# pcb-name-card.net
KiCad netlist of a schematic drawn in EAGLE
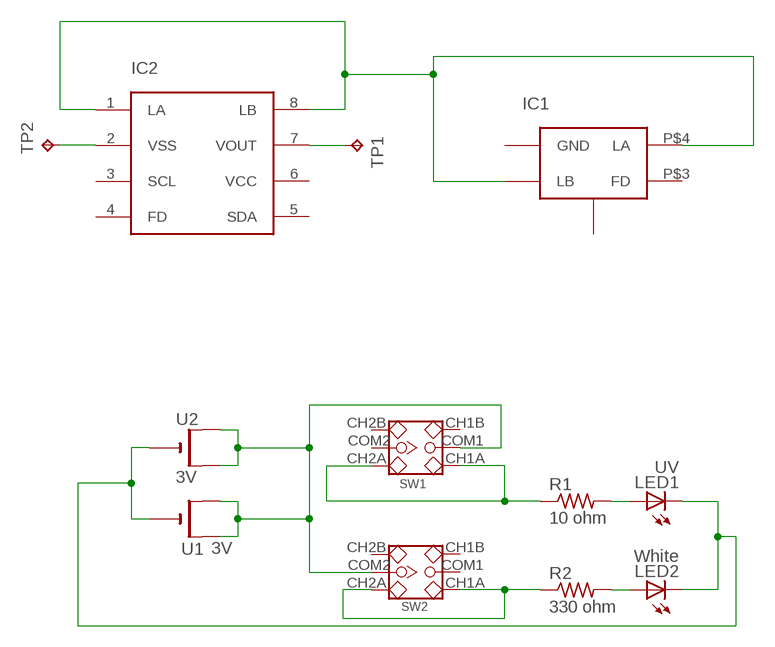
[diagram p0: schematic, sheet 1]

(export (version "E")
  (design (tool "Eeschema 10.0.6"))
  (components
    (comp (ref "IC1")
      (value "NTAG21XFDRC-FIT")
      (footprint "eagle-import:HXSON4-SMALL")
      (libsource (lib "eagle-import") (part "NTAG21XFDRC-FIT"))
    )
    (comp (ref "IC2")
      (value "NT3H1X01W0FTT")
      (footprint "eagle-import:TSSOP-8")
      (libsource (lib "eagle-import") (part "NT3H1X01W0FTT"))
    )
    (comp (ref "LED1")
      (value "UV")
      (footprint "eagle-import:PLCC2")
      (libsource (lib "eagle-import") (part "_T679-?-1D2E2LY"))
    )
    (comp (ref "LED2")
      (value "White")
      (footprint "eagle-import:PLCC2")
      (libsource (lib "eagle-import") (part "_T679-?-1D2E2LY"))
    )
    (comp (ref "R1")
      (value "10 ohm")
      (footprint "eagle-import:R2010")
      (libsource (lib "eagle-import") (part "R-US_R2010"))
    )
    (comp (ref "R2")
      (value "330 ohm")
      (footprint "eagle-import:R2010")
      (libsource (lib "eagle-import") (part "R-US_R2010"))
    )
    (comp (ref "SW1")
      (value "SMD-TOGGLE-SWITCH-2CH(2X3P-7X3.5MM)")
      (footprint "eagle-import:SW6-2.54-SMD-7.0X3.5X1.5MM")
      (fields (field (name "MPN") "MS-22C01"))
      (libsource (lib "eagle-import") (part "SMD-TOGGLE-SWITCH-2CH(2X3P-7X3.5MM)"))
    )
    (comp (ref "SW2")
      (value "SMD-TOGGLE-SWITCH-2CH(2X3P-7X3.5MM)")
      (footprint "eagle-import:SW6-2.54-SMD-7.0X3.5X1.5MM")
      (fields (field (name "MPN") "MS-22C01"))
      (libsource (lib "eagle-import") (part "SMD-TOGGLE-SWITCH-2CH(2X3P-7X3.5MM)"))
    )
    (comp (ref "TP1")
      (value "VOUT")
      (footprint "eagle-import:B2,54")
      (libsource (lib "eagle-import") (part "TPB2,54"))
    )
    (comp (ref "TP2")
      (value "GND")
      (footprint "eagle-import:B2,54")
      (libsource (lib "eagle-import") (part "TPB2,54"))
    )
    (comp (ref "U1")
      (value "3V")
      (footprint "eagle-import:CR2032-SMD")
      (libsource (lib "eagle-import") (part "CR2032SMT"))
    )
    (comp (ref "U2")
      (value "3V")
      (footprint "eagle-import:CR2032-SMD")
      (libsource (lib "eagle-import") (part "CR2032SMT"))
    )
  )
  (nets
    (net (code "1") (name "Net-(IC1-LA)") (class "Default")
      (node (ref "IC1") (pin "P$2") (pinfunction "LB_P$2") (pintype "bidirectional"))
      (node (ref "IC1") (pin "P$4") (pinfunction "LA_P$4") (pintype "bidirectional"))
      (node (ref "IC2") (pin "1") (pinfunction "LA_1") (pintype "bidirectional"))
      (node (ref "IC2") (pin "8") (pinfunction "LB_8") (pintype "bidirectional"))
    )
    (net (code "2") (name "Net-(IC2-VOUT)") (class "Default")
      (node (ref "IC2") (pin "7") (pinfunction "VOUT_7") (pintype "bidirectional"))
      (node (ref "TP1") (pin "TP") (pinfunction "TP_TP") (pintype "input"))
    )
    (net (code "3") (name "Net-(IC2-VSS)") (class "Default")
      (node (ref "IC2") (pin "2") (pinfunction "VSS_2") (pintype "bidirectional"))
      (node (ref "TP2") (pin "TP") (pinfunction "TP_TP") (pintype "input"))
    )
    (net (code "4") (name "Net-(LED1-PadA)") (class "Default")
      (node (ref "LED1") (pin "A") (pinfunction "A_A") (pintype "passive"))
      (node (ref "R1") (pin "2") (pinfunction "2_2") (pintype "passive"))
    )
    (net (code "5") (name "Net-(LED1-PadC)") (class "Default")
      (node (ref "LED1") (pin "C") (pinfunction "C_C") (pintype "passive"))
      (node (ref "LED2") (pin "C") (pinfunction "C_C") (pintype "passive"))
      (node (ref "U1") (pin "-") (pinfunction "-_-") (pintype "passive"))
      (node (ref "U2") (pin "-") (pinfunction "-_-") (pintype "passive"))
    )
    (net (code "6") (name "Net-(LED2-PadA)") (class "Default")
      (node (ref "LED2") (pin "A") (pinfunction "A_A") (pintype "passive"))
      (node (ref "R2") (pin "2") (pinfunction "2_2") (pintype "passive"))
    )
    (net (code "7") (name "Net-(R1-Pad1)") (class "Default")
      (node (ref "R1") (pin "1") (pinfunction "1_1") (pintype "passive"))
      (node (ref "SW1") (pin "CH1A") (pinfunction "CH1A_CH1A") (pintype "bidirectional"))
      (node (ref "SW1") (pin "CH2A") (pinfunction "CH2A_CH2A") (pintype "bidirectional"))
    )
    (net (code "8") (name "Net-(R2-Pad1)") (class "Default")
      (node (ref "R2") (pin "1") (pinfunction "1_1") (pintype "passive"))
      (node (ref "SW2") (pin "CH1A") (pinfunction "CH1A_CH1A") (pintype "bidirectional"))
      (node (ref "SW2") (pin "CH2A") (pinfunction "CH2A_CH2A") (pintype "bidirectional"))
    )
    (net (code "9") (name "Net-(U1-+)") (class "Default")
      (node (ref "SW1") (pin "COM1") (pinfunction "COM1_COM1") (pintype "bidirectional"))
      (node (ref "SW2") (pin "COM2") (pinfunction "COM2_COM2") (pintype "bidirectional"))
      (node (ref "U1") (pin "+$1") (pinfunction "+_+$1") (pintype "passive"))
      (node (ref "U1") (pin "+$2") (pinfunction "+1_+$2") (pintype "passive"))
      (node (ref "U2") (pin "+$1") (pinfunction "+_+$1") (pintype "passive"))
      (node (ref "U2") (pin "+$2") (pinfunction "+1_+$2") (pintype "passive"))
    )
    (net (code "10") (name "unconnected-(IC1-FD-PadP$3)") (class "Default")
      (node (ref "IC1") (pin "P$3") (pinfunction "FD_P$3") (pintype "bidirectional"))
    )
    (net (code "11") (name "unconnected-(IC1-FLOAT-PadP$5)") (class "Default")
      (node (ref "IC1") (pin "P$5") (pinfunction "FLOAT_P$5") (pintype "bidirectional"))
    )
    (net (code "12") (name "unconnected-(IC1-GND-PadP$1)") (class "Default")
      (node (ref "IC1") (pin "P$1") (pinfunction "GND_P$1") (pintype "bidirectional"))
    )
    (net (code "13") (name "unconnected-(IC2-FD-Pad4)") (class "Default")
      (node (ref "IC2") (pin "4") (pinfunction "FD_4") (pintype "bidirectional"))
    )
    (net (code "14") (name "unconnected-(IC2-SCL-Pad3)") (class "Default")
      (node (ref "IC2") (pin "3") (pinfunction "SCL_3") (pintype "bidirectional"))
    )
    (net (code "15") (name "unconnected-(IC2-SDA-Pad5)") (class "Default")
      (node (ref "IC2") (pin "5") (pinfunction "SDA_5") (pintype "bidirectional"))
    )
    (net (code "16") (name "unconnected-(IC2-VCC-Pad6)") (class "Default")
      (node (ref "IC2") (pin "6") (pinfunction "VCC_6") (pintype "bidirectional"))
    )
    (net (code "17") (name "unconnected-(SW1-PadCH1B)") (class "Default")
      (node (ref "SW1") (pin "CH1B") (pinfunction "CH1B_CH1B") (pintype "bidirectional"))
    )
    (net (code "18") (name "unconnected-(SW1-PadCH2B)") (class "Default")
      (node (ref "SW1") (pin "CH2B") (pinfunction "CH2B_CH2B") (pintype "bidirectional"))
    )
    (net (code "19") (name "unconnected-(SW1-PadCOM2)") (class "Default")
      (node (ref "SW1") (pin "COM2") (pinfunction "COM2_COM2") (pintype "bidirectional"))
    )
    (net (code "20") (name "unconnected-(SW2-PadCH1B)") (class "Default")
      (node (ref "SW2") (pin "CH1B") (pinfunction "CH1B_CH1B") (pintype "bidirectional"))
    )
    (net (code "21") (name "unconnected-(SW2-PadCH2B)") (class "Default")
      (node (ref "SW2") (pin "CH2B") (pinfunction "CH2B_CH2B") (pintype "bidirectional"))
    )
    (net (code "22") (name "unconnected-(SW2-PadCOM1)") (class "Default")
      (node (ref "SW2") (pin "COM1") (pinfunction "COM1_COM1") (pintype "bidirectional"))
    )
  )
)
